# untitled.net
KiCad netlist of a schematic drawn in EAGLE
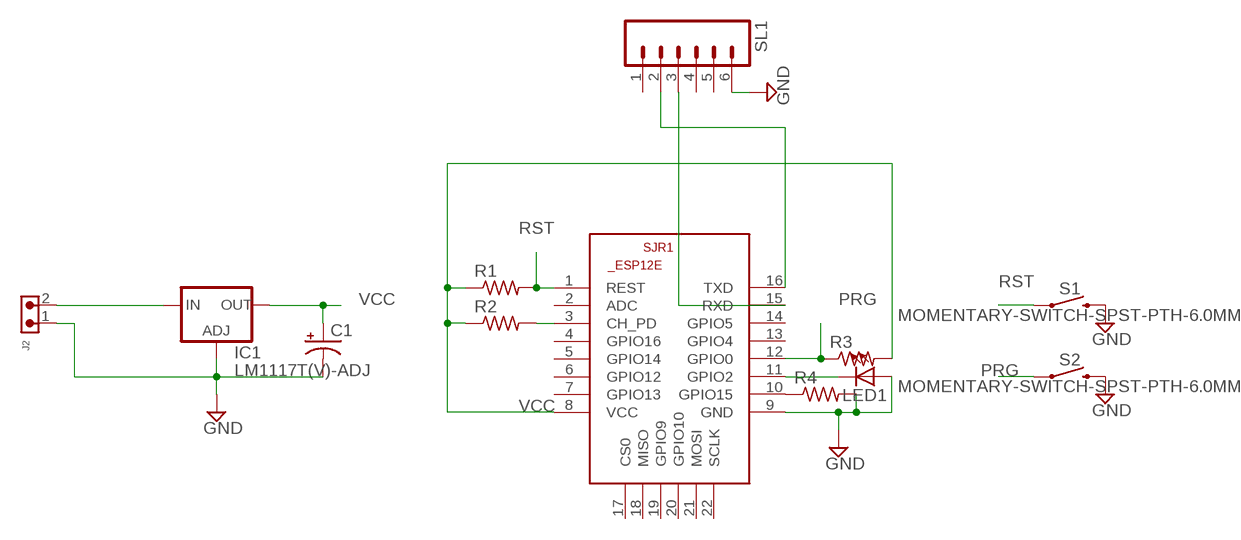
[diagram p0: schematic, sheet 1]

(export (version "E")
  (design (tool "Eeschema 10.0.6"))
  (components
    (comp (ref "C1")
      (value "CAPACITOR-PE5-10.5")
      (footprint "eagle-import:E5-10,5")
      (libsource (lib "eagle-import") (part "CAPACITOR-PE5-10.5"))
    )
    (comp (ref "IC1")
      (value "LM1117T(V)-ADJ")
      (footprint "eagle-import:TO220V")
      (fields (field (name "MF") "Texas Instruments") (field (name "MPN") "LM1777T-ADJ"))
      (libsource (lib "eagle-import") (part "LM1117?-ADJT(V)"))
    )
    (comp (ref "J2")
      (value "691305530002")
      (footprint "eagle-import:691305530002")
      (libsource (lib "eagle-import") (part "691305530002"))
    )
    (comp (ref "LED1")
      (value "LED5MM")
      (footprint "eagle-import:LED5MM")
      (libsource (lib "eagle-import") (part "LED5MM"))
    )
    (comp (ref "R1")
      (value "R-US_0207/10")
      (footprint "eagle-import:0207_10")
      (libsource (lib "eagle-import") (part "R-US_0207/10"))
    )
    (comp (ref "R2")
      (value "R-US_0207/10")
      (footprint "eagle-import:0207_10")
      (libsource (lib "eagle-import") (part "R-US_0207/10"))
    )
    (comp (ref "R3")
      (value "R-US_0207/10")
      (footprint "eagle-import:0207_10")
      (libsource (lib "eagle-import") (part "R-US_0207/10"))
    )
    (comp (ref "R4")
      (value "R-US_0207/10")
      (footprint "eagle-import:0207_10")
      (libsource (lib "eagle-import") (part "R-US_0207/10"))
    )
    (comp (ref "S1")
      (value "MOMENTARY-SWITCH-SPST-PTH-6.0MM")
      (footprint "eagle-import:TACTILE_SWITCH_PTH_6.0MM")
      (libsource (lib "eagle-import") (part "MOMENTARY-SWITCH-SPST-PTH-6.0MM"))
    )
    (comp (ref "S2")
      (value "MOMENTARY-SWITCH-SPST-PTH-6.0MM")
      (footprint "eagle-import:TACTILE_SWITCH_PTH_6.0MM")
      (libsource (lib "eagle-import") (part "MOMENTARY-SWITCH-SPST-PTH-6.0MM"))
    )
    (comp (ref "SJR1")
      (value "ESP8266-12EESP12E")
      (footprint "eagle-import:ESP8266-ESP12E")
      (libsource (lib "eagle-import") (part "ESP8266-12EESP12E"))
    )
    (comp (ref "SL1")
      (value "M06")
      (footprint "eagle-import:06P")
      (libsource (lib "eagle-import") (part "M06"))
    )
  )
  (nets
    (net (code "1") (name "/PRG") (class "Default")
      (node (ref "R3") (pin "1") (pinfunction "1_1") (pintype "passive"))
      (node (ref "S2") (pin "1") (pinfunction "1_1") (pintype "passive"))
      (node (ref "SJR1") (pin "12") (pinfunction "GPIO0_12") (pintype "bidirectional"))
    )
    (net (code "2") (name "/RST") (class "Default")
      (node (ref "R1") (pin "2") (pinfunction "2_2") (pintype "passive"))
      (node (ref "S1") (pin "1") (pinfunction "1_1") (pintype "passive"))
      (node (ref "SJR1") (pin "1") (pinfunction "REST_1") (pintype "bidirectional"))
    )
    (net (code "3") (name "/VCC") (class "Default")
      (node (ref "C1") (pin "+") (pinfunction "+_+") (pintype "passive"))
      (node (ref "IC1") (pin "2") (pinfunction "OUT_2") (pintype "passive"))
      (node (ref "R1") (pin "1") (pinfunction "1_1") (pintype "passive"))
      (node (ref "R2") (pin "1") (pinfunction "1_1") (pintype "passive"))
      (node (ref "R3") (pin "2") (pinfunction "2_2") (pintype "passive"))
      (node (ref "SJR1") (pin "8") (pinfunction "VCC_8") (pintype "bidirectional"))
    )
    (net (code "4") (name "GND") (class "Default")
      (node (ref "C1") (pin "-") (pinfunction "-_-") (pintype "passive"))
      (node (ref "IC1") (pin "1") (pinfunction "ADJ_1") (pintype "input"))
      (node (ref "J2") (pin "1") (pinfunction "1_1") (pintype "passive"))
      (node (ref "LED1") (pin "A") (pinfunction "A_A") (pintype "passive"))
      (node (ref "R4") (pin "2") (pinfunction "2_2") (pintype "passive"))
      (node (ref "S1") (pin "3") (pinfunction "2_3") (pintype "passive"))
      (node (ref "S2") (pin "3") (pinfunction "2_3") (pintype "passive"))
      (node (ref "SJR1") (pin "9") (pinfunction "GND_9") (pintype "bidirectional"))
      (node (ref "SL1") (pin "6") (pinfunction "6_6") (pintype "passive"))
    )
    (net (code "5") (name "Net-(IC1-IN)") (class "Default")
      (node (ref "IC1") (pin "3") (pinfunction "IN_3") (pintype "input"))
      (node (ref "J2") (pin "2") (pinfunction "2_2") (pintype "passive"))
    )
    (net (code "6") (name "Net-(LED1-C)") (class "Default")
      (node (ref "LED1") (pin "K") (pinfunction "C_K") (pintype "passive"))
      (node (ref "SJR1") (pin "11") (pinfunction "GPIO2_11") (pintype "bidirectional"))
    )
    (net (code "7") (name "Net-(SJR1-CH_PD)") (class "Default")
      (node (ref "R2") (pin "2") (pinfunction "2_2") (pintype "passive"))
      (node (ref "SJR1") (pin "3") (pinfunction "CH_PD_3") (pintype "bidirectional"))
    )
    (net (code "8") (name "Net-(SJR1-GPIO15)") (class "Default")
      (node (ref "R4") (pin "1") (pinfunction "1_1") (pintype "passive"))
      (node (ref "SJR1") (pin "10") (pinfunction "GPIO15_10") (pintype "bidirectional"))
    )
    (net (code "9") (name "Net-(SJR1-RXD)") (class "Default")
      (node (ref "SJR1") (pin "15") (pinfunction "RXD_15") (pintype "bidirectional"))
      (node (ref "SL1") (pin "3") (pinfunction "3_3") (pintype "passive"))
    )
    (net (code "10") (name "Net-(SJR1-TXD)") (class "Default")
      (node (ref "SJR1") (pin "16") (pinfunction "TXD_16") (pintype "bidirectional"))
      (node (ref "SL1") (pin "2") (pinfunction "2_2") (pintype "passive"))
    )
    (net (code "11") (name "unconnected-(SJR1-ADC-Pad2)") (class "Default")
      (node (ref "SJR1") (pin "2") (pinfunction "ADC_2") (pintype "bidirectional"))
    )
    (net (code "12") (name "unconnected-(SJR1-CS0-Pad17)") (class "Default")
      (node (ref "SJR1") (pin "17") (pinfunction "CS0_17") (pintype "bidirectional"))
    )
    (net (code "13") (name "unconnected-(SJR1-GPIO4-Pad13)") (class "Default")
      (node (ref "SJR1") (pin "13") (pinfunction "GPIO4_13") (pintype "bidirectional"))
    )
    (net (code "14") (name "unconnected-(SJR1-GPIO5-Pad14)") (class "Default")
      (node (ref "SJR1") (pin "14") (pinfunction "GPIO5_14") (pintype "bidirectional"))
    )
    (net (code "15") (name "unconnected-(SJR1-GPIO9-Pad19)") (class "Default")
      (node (ref "SJR1") (pin "19") (pinfunction "GPIO9_19") (pintype "bidirectional"))
    )
    (net (code "16") (name "unconnected-(SJR1-GPIO10-Pad20)") (class "Default")
      (node (ref "SJR1") (pin "20") (pinfunction "GPIO10_20") (pintype "bidirectional"))
    )
    (net (code "17") (name "unconnected-(SJR1-GPIO12-Pad6)") (class "Default")
      (node (ref "SJR1") (pin "6") (pinfunction "GPIO12_6") (pintype "bidirectional"))
    )
    (net (code "18") (name "unconnected-(SJR1-GPIO13-Pad7)") (class "Default")
      (node (ref "SJR1") (pin "7") (pinfunction "GPIO13_7") (pintype "bidirectional"))
    )
    (net (code "19") (name "unconnected-(SJR1-GPIO14-Pad5)") (class "Default")
      (node (ref "SJR1") (pin "5") (pinfunction "GPIO14_5") (pintype "bidirectional"))
    )
    (net (code "20") (name "unconnected-(SJR1-GPIO16-Pad4)") (class "Default")
      (node (ref "SJR1") (pin "4") (pinfunction "GPIO16_4") (pintype "bidirectional"))
    )
    (net (code "21") (name "unconnected-(SJR1-MISO-Pad18)") (class "Default")
      (node (ref "SJR1") (pin "18") (pinfunction "MISO_18") (pintype "bidirectional"))
    )
    (net (code "22") (name "unconnected-(SJR1-MOSI-Pad21)") (class "Default")
      (node (ref "SJR1") (pin "21") (pinfunction "MOSI_21") (pintype "bidirectional"))
    )
    (net (code "23") (name "unconnected-(SJR1-SCLK-Pad22)") (class "Default")
      (node (ref "SJR1") (pin "22") (pinfunction "SCLK_22") (pintype "bidirectional"))
    )
    (net (code "24") (name "unconnected-(SL1-Pad1)") (class "Default")
      (node (ref "SL1") (pin "1") (pinfunction "1_1") (pintype "passive"))
    )
    (net (code "25") (name "unconnected-(SL1-Pad4)") (class "Default")
      (node (ref "SL1") (pin "4") (pinfunction "4_4") (pintype "passive"))
    )
    (net (code "26") (name "unconnected-(SL1-Pad5)") (class "Default")
      (node (ref "SL1") (pin "5") (pinfunction "5_5") (pintype "passive"))
    )
  )
)
